# hvsupply.net
KiCad netlist of a schematic drawn in EAGLE
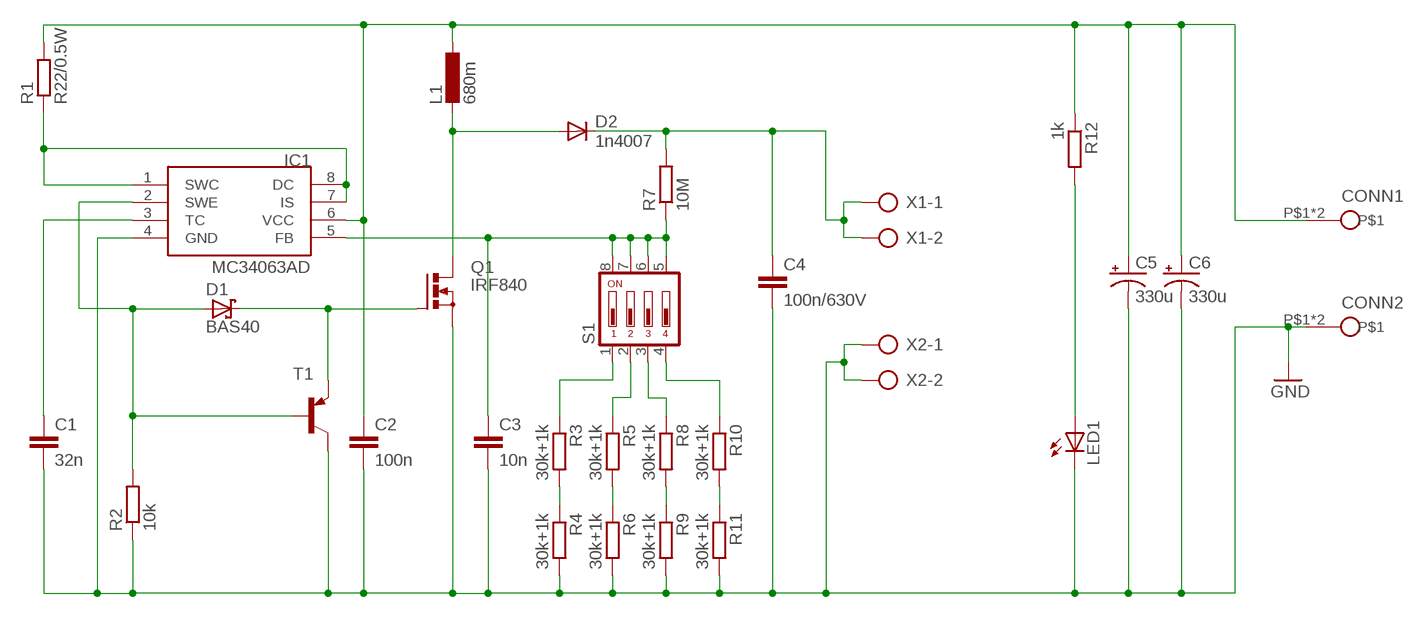
[diagram p0: schematic, sheet 1]

(export (version "E")
  (design (tool "Eeschema 10.0.6"))
  (components
    (comp (ref "11")
      (value "BANANA-PLUG-2-PADS")
      (footprint "eagle-import:BANANA-PLUG-2-PADS")
      (fields (field (name "PREFIX") "CONN1"))
      (libsource (lib "eagle-import") (part "BANANA-PLUG-2-PADS"))
    )
    (comp (ref "12")
      (value "BANANA-PLUG-2-PADS")
      (footprint "eagle-import:BANANA-PLUG-2-PADS")
      (fields (field (name "PREFIX") "CONN2"))
      (libsource (lib "eagle-import") (part "BANANA-PLUG-2-PADS"))
    )
    (comp (ref "C1")
      (value "32n")
      (footprint "eagle-import:C025-025X050")
      (libsource (lib "eagle-import") (part "C-EU025-025X050"))
    )
    (comp (ref "C2")
      (value "100n")
      (footprint "eagle-import:C3216")
      (libsource (lib "eagle-import") (part "C-EUC3216"))
    )
    (comp (ref "C3")
      (value "10n")
      (footprint "eagle-import:C3216")
      (libsource (lib "eagle-import") (part "C-EUC3216"))
    )
    (comp (ref "C4")
      (value "100n/630V")
      (footprint "eagle-import:C102-064X133")
      (libsource (lib "eagle-import") (part "C-EU102-064X133"))
    )
    (comp (ref "C5")
      (value "330u")
      (footprint "eagle-import:A_3216-18W")
      (libsource (lib "eagle-import") (part "CPOL-USA/3216-18W"))
    )
    (comp (ref "C6")
      (value "330u")
      (footprint "eagle-import:A_3216-18W")
      (libsource (lib "eagle-import") (part "CPOL-USA/3216-18W"))
    )
    (comp (ref "D1")
      (value "BAS40")
      (footprint "eagle-import:SOT23")
      (libsource (lib "eagle-import") (part "BAS40"))
    )
    (comp (ref "D2")
      (value "1n4007")
      (footprint "eagle-import:DO41-10")
      (libsource (lib "eagle-import") (part "1N4004"))
    )
    (comp (ref "IC1")
      (value "MC34063AD")
      (footprint "eagle-import:SOIC8")
      (libsource (lib "eagle-import") (part "MC34063AD"))
    )
    (comp (ref "L1")
      (value "680m")
      (footprint "eagle-import:0207_5V")
      (libsource (lib "eagle-import") (part "L-EU0207/5V"))
    )
    (comp (ref "LED1")
      (value "LED3MM")
      (footprint "eagle-import:LED3MM")
      (libsource (lib "eagle-import") (part "LED3MM"))
    )
    (comp (ref "Q1")
      (value "IRF840")
      (footprint "eagle-import:TO220BV")
      (libsource (lib "eagle-import") (part "BUZ11BV"))
    )
    (comp (ref "R1")
      (value "R22/0.5W")
      (footprint "eagle-import:0207_5V")
      (libsource (lib "eagle-import") (part "R-EU_0207/5V"))
    )
    (comp (ref "R2")
      (value "10k")
      (footprint "eagle-import:R1206")
      (libsource (lib "eagle-import") (part "R-EU_R1206"))
    )
    (comp (ref "R3")
      (value "30k+1k")
      (footprint "eagle-import:R1206")
      (libsource (lib "eagle-import") (part "R-EU_R1206"))
    )
    (comp (ref "R4")
      (value "30k+1k")
      (footprint "eagle-import:R1206")
      (libsource (lib "eagle-import") (part "R-EU_R1206"))
    )
    (comp (ref "R5")
      (value "30k+1k")
      (footprint "eagle-import:R1206")
      (libsource (lib "eagle-import") (part "R-EU_R1206"))
    )
    (comp (ref "R6")
      (value "30k+1k")
      (footprint "eagle-import:R1206")
      (libsource (lib "eagle-import") (part "R-EU_R1206"))
    )
    (comp (ref "R7")
      (value "10M")
      (footprint "eagle-import:0207_5V")
      (libsource (lib "eagle-import") (part "R-EU_0207/5V"))
    )
    (comp (ref "R8")
      (value "30k+1k")
      (footprint "eagle-import:R1206")
      (libsource (lib "eagle-import") (part "R-EU_R1206"))
    )
    (comp (ref "R9")
      (value "30k+1k")
      (footprint "eagle-import:R1206")
      (libsource (lib "eagle-import") (part "R-EU_R1206"))
    )
    (comp (ref "R10")
      (value "30k+1k")
      (footprint "eagle-import:R1206")
      (libsource (lib "eagle-import") (part "R-EU_R1206"))
    )
    (comp (ref "R11")
      (value "30k+1k")
      (footprint "eagle-import:R1206")
      (libsource (lib "eagle-import") (part "R-EU_R1206"))
    )
    (comp (ref "R12")
      (value "1k")
      (footprint "eagle-import:R1206")
      (libsource (lib "eagle-import") (part "R-EU_R1206"))
    )
    (comp (ref "S1")
      (value "DS04")
      (footprint "eagle-import:DS-04")
      (libsource (lib "eagle-import") (part "DS04"))
    )
    (comp (ref "T1")
      (value "BC807-40-PNP-SOT23-BEC")
      (footprint "eagle-import:SOT23-BEC")
      (libsource (lib "eagle-import") (part "-PNP-SOT23-BECBC807-40"))
    )
    (comp (ref "X1")
      (value "AK500/2-H")
      (footprint "eagle-import:AK500_2-H")
      (libsource (lib "eagle-import") (part "AK500/2-H"))
    )
    (comp (ref "X2")
      (value "AK500/2-H")
      (footprint "eagle-import:AK500_2-H")
      (libsource (lib "eagle-import") (part "AK500/2-H"))
    )
  )
  (nets
    (net (code "1") (name "GND") (class "Default")
      (node (ref "12") (pin "P$1") (pinfunction "P$1_P$1") (pintype "bidirectional"))
      (node (ref "12") (pin "P$2") (pinfunction "P$1_P$2") (pintype "bidirectional"))
      (node (ref "C1") (pin "2") (pinfunction "2_2") (pintype "passive"))
      (node (ref "C2") (pin "2") (pinfunction "2_2") (pintype "passive"))
      (node (ref "C3") (pin "2") (pinfunction "2_2") (pintype "passive"))
      (node (ref "C4") (pin "2") (pinfunction "2_2") (pintype "passive"))
      (node (ref "C5") (pin "-") (pinfunction "-_-") (pintype "passive"))
      (node (ref "C6") (pin "-") (pinfunction "-_-") (pintype "passive"))
      (node (ref "IC1") (pin "4") (pinfunction "GND_4") (pintype "passive"))
      (node (ref "LED1") (pin "K") (pinfunction "C_K") (pintype "passive"))
      (node (ref "Q1") (pin "S") (pinfunction "S_S") (pintype "passive"))
      (node (ref "R11") (pin "2") (pinfunction "2_2") (pintype "passive"))
      (node (ref "R2") (pin "1") (pinfunction "1_1") (pintype "passive"))
      (node (ref "R4") (pin "2") (pinfunction "2_2") (pintype "passive"))
      (node (ref "R6") (pin "2") (pinfunction "2_2") (pintype "passive"))
      (node (ref "R9") (pin "2") (pinfunction "2_2") (pintype "passive"))
      (node (ref "T1") (pin "C") (pinfunction "C_C") (pintype "passive"))
      (node (ref "X2") (pin "1") (pinfunction "KL_1") (pintype "passive"))
      (node (ref "X2") (pin "2") (pinfunction "KL_2") (pintype "passive"))
    )
    (net (code "2") (name "Net-(D1-A)") (class "Default")
      (node (ref "D1") (pin "1") (pinfunction "A_1") (pintype "passive"))
      (node (ref "IC1") (pin "2") (pinfunction "SWE_2") (pintype "passive"))
      (node (ref "R2") (pin "2") (pinfunction "2_2") (pintype "passive"))
      (node (ref "T1") (pin "B") (pinfunction "B_B") (pintype "passive"))
    )
    (net (code "3") (name "Net-(D1-C)") (class "Default")
      (node (ref "D1") (pin "3") (pinfunction "C_3") (pintype "passive"))
      (node (ref "Q1") (pin "G") (pinfunction "G_G") (pintype "passive"))
      (node (ref "T1") (pin "E") (pinfunction "E_E") (pintype "passive"))
    )
    (net (code "4") (name "Net-(D2-PadA)") (class "Default")
      (node (ref "D2") (pin "A") (pinfunction "A_A") (pintype "passive"))
      (node (ref "L1") (pin "2") (pinfunction "2_2") (pintype "passive"))
      (node (ref "Q1") (pin "D") (pinfunction "D_D") (pintype "passive"))
    )
    (net (code "5") (name "Net-(IC1-DC)") (class "Default")
      (node (ref "IC1") (pin "1") (pinfunction "SWC_1") (pintype "passive"))
      (node (ref "IC1") (pin "7") (pinfunction "IS_7") (pintype "passive"))
      (node (ref "IC1") (pin "8") (pinfunction "DC_8") (pintype "passive"))
      (node (ref "R1") (pin "1") (pinfunction "1_1") (pintype "passive"))
    )
    (net (code "6") (name "Net-(IC1-FB)") (class "Default")
      (node (ref "C3") (pin "1") (pinfunction "1_1") (pintype "passive"))
      (node (ref "IC1") (pin "5") (pinfunction "FB_5") (pintype "passive"))
      (node (ref "R7") (pin "1") (pinfunction "1_1") (pintype "passive"))
      (node (ref "S1") (pin "5") (pinfunction "5_5") (pintype "passive"))
      (node (ref "S1") (pin "6") (pinfunction "6_6") (pintype "passive"))
      (node (ref "S1") (pin "7") (pinfunction "7_7") (pintype "passive"))
      (node (ref "S1") (pin "8") (pinfunction "8_8") (pintype "passive"))
    )
    (net (code "7") (name "Net-(IC1-TC)") (class "Default")
      (node (ref "C1") (pin "1") (pinfunction "1_1") (pintype "passive"))
      (node (ref "IC1") (pin "3") (pinfunction "TC_3") (pintype "passive"))
    )
    (net (code "8") (name "Net-(IC1-VCC)") (class "Default")
      (node (ref "11") (pin "P$1") (pinfunction "P$1_P$1") (pintype "bidirectional"))
      (node (ref "11") (pin "P$2") (pinfunction "P$1_P$2") (pintype "bidirectional"))
      (node (ref "C2") (pin "1") (pinfunction "1_1") (pintype "passive"))
      (node (ref "C5") (pin "+") (pinfunction "+_+") (pintype "passive"))
      (node (ref "C6") (pin "+") (pinfunction "+_+") (pintype "passive"))
      (node (ref "IC1") (pin "6") (pinfunction "VCC_6") (pintype "passive"))
      (node (ref "L1") (pin "1") (pinfunction "1_1") (pintype "passive"))
      (node (ref "R1") (pin "2") (pinfunction "2_2") (pintype "passive"))
      (node (ref "R12") (pin "1") (pinfunction "1_1") (pintype "passive"))
    )
    (net (code "9") (name "Net-(LED1-PadA)") (class "Default")
      (node (ref "LED1") (pin "A") (pinfunction "A_A") (pintype "passive"))
      (node (ref "R12") (pin "2") (pinfunction "2_2") (pintype "passive"))
    )
    (net (code "10") (name "Net-(R3-Pad1)") (class "Default")
      (node (ref "R3") (pin "1") (pinfunction "1_1") (pintype "passive"))
      (node (ref "S1") (pin "1") (pinfunction "1_1") (pintype "passive"))
    )
    (net (code "11") (name "Net-(R3-Pad2)") (class "Default")
      (node (ref "R3") (pin "2") (pinfunction "2_2") (pintype "passive"))
      (node (ref "R4") (pin "1") (pinfunction "1_1") (pintype "passive"))
    )
    (net (code "12") (name "Net-(R5-Pad1)") (class "Default")
      (node (ref "R5") (pin "1") (pinfunction "1_1") (pintype "passive"))
      (node (ref "S1") (pin "2") (pinfunction "2_2") (pintype "passive"))
    )
    (net (code "13") (name "Net-(R5-Pad2)") (class "Default")
      (node (ref "R5") (pin "2") (pinfunction "2_2") (pintype "passive"))
      (node (ref "R6") (pin "1") (pinfunction "1_1") (pintype "passive"))
    )
    (net (code "14") (name "Net-(R8-Pad1)") (class "Default")
      (node (ref "R8") (pin "1") (pinfunction "1_1") (pintype "passive"))
      (node (ref "S1") (pin "3") (pinfunction "3_3") (pintype "passive"))
    )
    (net (code "15") (name "Net-(R8-Pad2)") (class "Default")
      (node (ref "R8") (pin "2") (pinfunction "2_2") (pintype "passive"))
      (node (ref "R9") (pin "1") (pinfunction "1_1") (pintype "passive"))
    )
    (net (code "16") (name "Net-(R10-Pad1)") (class "Default")
      (node (ref "R10") (pin "1") (pinfunction "1_1") (pintype "passive"))
      (node (ref "S1") (pin "4") (pinfunction "4_4") (pintype "passive"))
    )
    (net (code "17") (name "Net-(R10-Pad2)") (class "Default")
      (node (ref "R10") (pin "2") (pinfunction "2_2") (pintype "passive"))
      (node (ref "R11") (pin "1") (pinfunction "1_1") (pintype "passive"))
    )
    (net (code "18") (name "Net-(X1A-KL)") (class "Default")
      (node (ref "C4") (pin "1") (pinfunction "1_1") (pintype "passive"))
      (node (ref "D2") (pin "C") (pinfunction "C_C") (pintype "passive"))
      (node (ref "R7") (pin "2") (pinfunction "2_2") (pintype "passive"))
      (node (ref "X1") (pin "1") (pinfunction "KL_1") (pintype "passive"))
      (node (ref "X1") (pin "2") (pinfunction "KL_2") (pintype "passive"))
    )
  )
)
